# OBwod_sterowania_STM32.net
KiCad netlist of a schematic drawn in Altium Designer
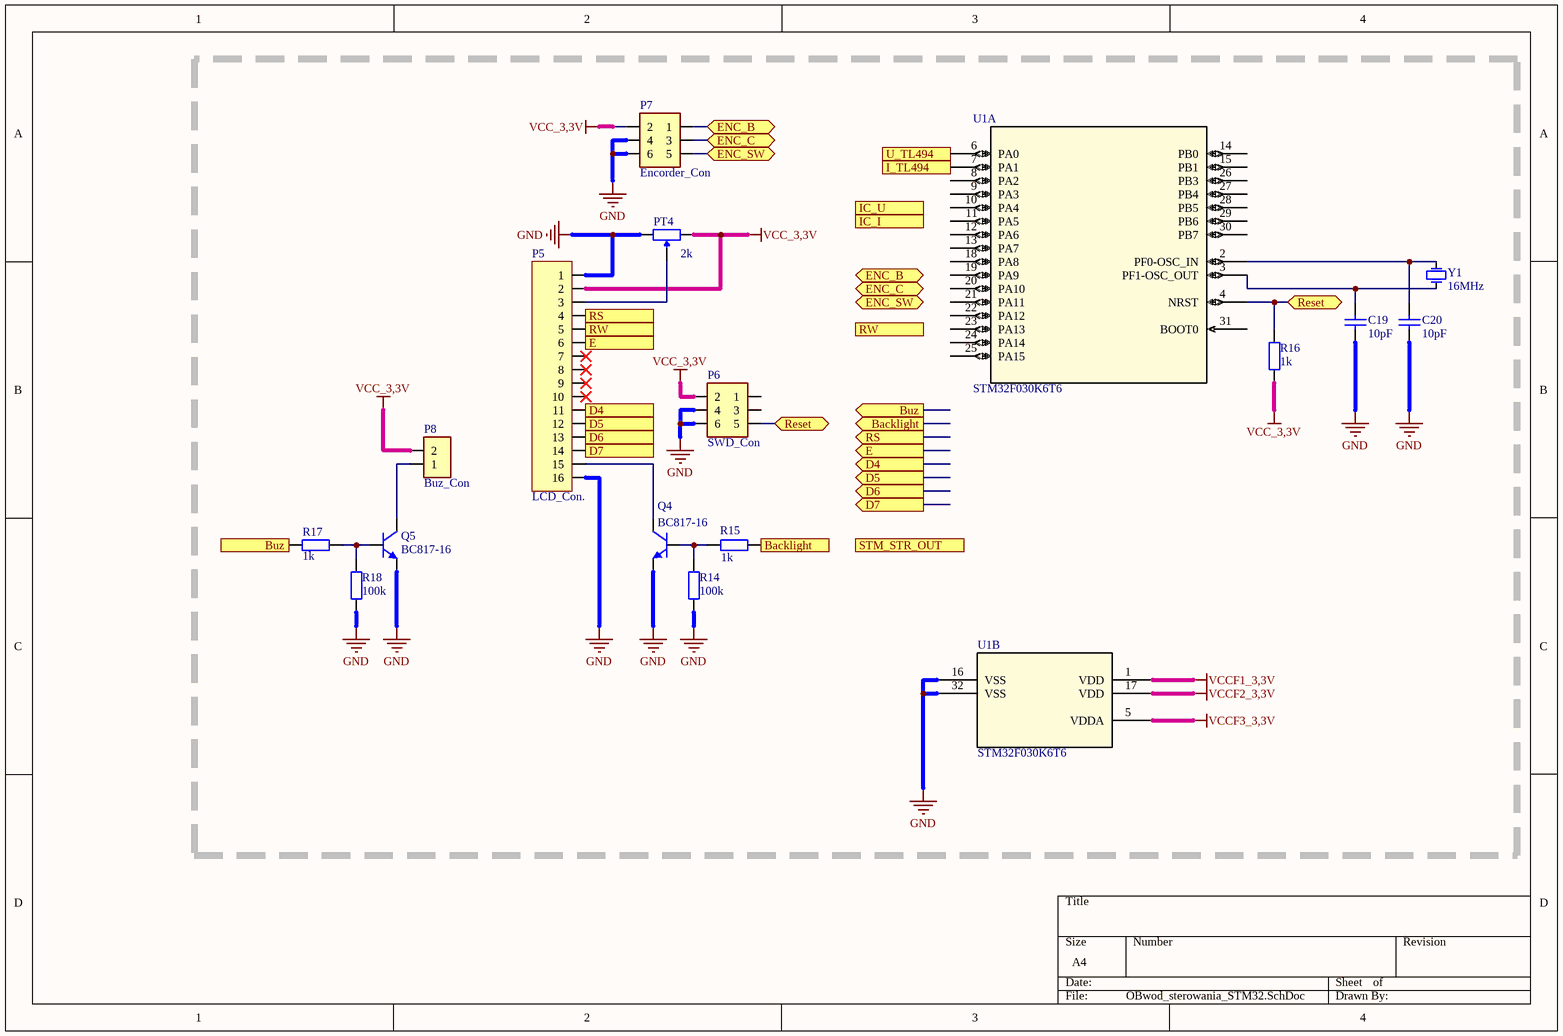
[diagram p0: OBwod_sterowania_STM32.SchDoc]

(export (version "E")
  (design (tool "Eeschema 10.0.6"))
  (components
    (comp (ref "C19")
      (value "Kondesator")
      (footprint "SMD-1206C")
      (fields (field (name "PARAMETR_1") "10pF"))
      (libsource (lib "MyLibrary") (part "Kondesator"))
    )
    (comp (ref "C20")
      (value "Kondesator")
      (footprint "SMD-1206C")
      (fields (field (name "PARAMETR_1") "10pF"))
      (libsource (lib "MyLibrary") (part "Kondesator"))
    )
    (comp (ref "P5")
      (value "LCD_Con.")
      (footprint "Header_Male 1x16")
      (description "Header, 16-Pin")
      (fields (field (name "PUBLISHER") "Altium Limited"))
      (libsource (lib "MyLibrary") (part "Header 16"))
    )
    (comp (ref "P6")
      (value "SWD_Con")
      (footprint "goldpin SMD 1,27")
      (libsource (lib "MyLibrary") (part "Header 2x3"))
    )
    (comp (ref "P7")
      (value "Encorder_Con")
      (footprint "Header_Male 2X3")
      (libsource (lib "MyLibrary") (part "Header 2x3"))
    )
    (comp (ref "P8")
      (value "Buz_Con")
      (footprint "Header_Male 1x2")
      (fields (field (name "PUBLISHER") "Altium Limited"))
      (libsource (lib "MyLibrary") (part "Header 2"))
    )
    (comp (ref "PT4")
      (value "Potentiometer")
      (footprint "Potecjomert")
      (description "Potentiometer montażowy wielobortowy")
      (fields (field (name "PARAMETR_1") "2k"))
      (libsource (lib "MyLibrary") (part "Potentiometer"))
    )
    (comp (ref "Q4")
      (value "BC817-16")
      (footprint "SOT323")
      (description "Tranzystor bipolarny PNP")
      (fields (field (name "OZNACZENIE") "BC817-16"))
      (libsource (lib "MyLibrary") (part "BC817-16"))
    )
    (comp (ref "Q5")
      (value "BC817-16")
      (footprint "SOT323")
      (description "Tranzystor bipolarny PNP")
      (fields (field (name "OZNACZENIE") "BC817-16"))
      (libsource (lib "MyLibrary") (part "BC817-16"))
    )
    (comp (ref "R14")
      (value "Rezystor")
      (footprint "SMD-1206-RES")
      (fields (field (name "PARAMETR_1") "100k"))
      (libsource (lib "") (part "Rezystor_1"))
    )
    (comp (ref "R15")
      (value "Rezystor")
      (footprint "SMD-1206-RES")
      (fields (field (name "PARAMETR_1") "1k"))
      (libsource (lib "MyLibrary") (part "Rezystor"))
    )
    (comp (ref "R16")
      (value "Rezystor")
      (footprint "SMD-1206-RES")
      (fields (field (name "PARAMETR_1") "1k"))
      (libsource (lib "") (part "Rezystor_2"))
    )
    (comp (ref "R17")
      (value "Rezystor")
      (footprint "SMD-1206-RES")
      (fields (field (name "PARAMETR_1") "1k"))
      (libsource (lib "") (part "Rezystor_2"))
    )
    (comp (ref "R18")
      (value "Rezystor")
      (footprint "SMD-1206-RES")
      (fields (field (name "PARAMETR_1") "100k"))
      (libsource (lib "MyLibrary") (part "Rezystor"))
    )
    (comp (ref "U1")
      (value "STM32F030K6T6")
      (footprint "LQFP-32")
      (description "No Description Available")
      (fields (field (name "COPYRIGHT") "Copyright (C) 2022 Ultra Librarian. All rights reserved."))
      (libsource (lib "MyLibrary") (part "STM32F030K6T6"))
    )
    (comp (ref "Y1") (value "16MHz") (footprint "HC49SM") (libsource (lib "MyLibrary") (part "Oscylator")))
  )
  (nets
    (net (code "1") (name "/Backlight") (class "Default")
      (node (ref "R15") (pin "1") (pinfunction "1_1") (pintype "passive"))
    )
    (net (code "2") (name "/Buz") (class "Default")
      (node (ref "R17") (pin "1") (pinfunction "1_1") (pintype "passive"))
    )
    (net (code "3") (name "/D4") (class "Default")
      (node (ref "P5") (pin "11") (pinfunction "11_11") (pintype "passive"))
    )
    (net (code "4") (name "/D5") (class "Default")
      (node (ref "P5") (pin "12") (pinfunction "12_12") (pintype "passive"))
    )
    (net (code "5") (name "/D6") (class "Default")
      (node (ref "P5") (pin "13") (pinfunction "13_13") (pintype "passive"))
    )
    (net (code "6") (name "/D7") (class "Default")
      (node (ref "P5") (pin "14") (pinfunction "14_14") (pintype "passive"))
    )
    (net (code "7") (name "/E") (class "Default")
      (node (ref "P5") (pin "6") (pinfunction "6_6") (pintype "passive"))
    )
    (net (code "8") (name "/ENC_B") (class "Default")
      (node (ref "P7") (pin "1") (pinfunction "1_1") (pintype "passive"))
    )
    (net (code "9") (name "/ENC_C") (class "Default")
      (node (ref "P7") (pin "3") (pinfunction "3_3") (pintype "passive"))
    )
    (net (code "10") (name "/ENC_SW") (class "Default")
      (node (ref "P7") (pin "5") (pinfunction "5_5") (pintype "passive"))
    )
    (net (code "13") (name "/I_TL494") (class "Default")
      (node (ref "U1") (pin "7") (pinfunction "PA1_7") (pintype "bidirectional"))
    )
    (net (code "14") (name "/RS") (class "Default")
      (node (ref "P5") (pin "4") (pinfunction "4_4") (pintype "passive"))
    )
    (net (code "15") (name "/RW") (class "Default")
      (node (ref "P5") (pin "5") (pinfunction "5_5") (pintype "passive"))
    )
    (net (code "16") (name "/Reset") (class "Default")
      (node (ref "P6") (pin "5") (pinfunction "5_5") (pintype "passive"))
      (node (ref "R16") (pin "2") (pinfunction "2_2") (pintype "passive"))
      (node (ref "U1") (pin "4") (pinfunction "NRST_4") (pintype "bidirectional"))
    )
    (net (code "18") (name "/U_TL494") (class "Default")
      (node (ref "U1") (pin "6") (pinfunction "PA0_6") (pintype "bidirectional"))
    )
    (net (code "19") (name "GND") (class "Default")
      (node (ref "C19") (pin "2") (pinfunction "2_2") (pintype "passive"))
      (node (ref "C20") (pin "1") (pinfunction "1_1") (pintype "passive"))
      (node (ref "P5") (pin "1") (pinfunction "1_1") (pintype "passive"))
      (node (ref "P5") (pin "16") (pinfunction "16_16") (pintype "passive"))
      (node (ref "P6") (pin "4") (pinfunction "4_4") (pintype "passive"))
      (node (ref "P6") (pin "6") (pinfunction "6_6") (pintype "passive"))
      (node (ref "P7") (pin "4") (pinfunction "4_4") (pintype "passive"))
      (node (ref "P7") (pin "6") (pinfunction "6_6") (pintype "passive"))
      (node (ref "PT4") (pin "1") (pinfunction "TOP_1") (pintype "passive"))
      (node (ref "Q4") (pin "2") (pinfunction "E_2") (pintype "passive"))
      (node (ref "Q5") (pin "2") (pinfunction "E_2") (pintype "passive"))
      (node (ref "R14") (pin "2") (pinfunction "2_2") (pintype "passive"))
      (node (ref "R18") (pin "2") (pinfunction "2_2") (pintype "passive"))
      (node (ref "U1") (pin "16") (pinfunction "VSS_16") (pintype "power_in"))
      (node (ref "U1") (pin "32") (pinfunction "VSS_32") (pintype "power_in"))
    )
    (net (code "20") (name "Net-(PT4-TAP)") (class "Default")
      (node (ref "P5") (pin "3") (pinfunction "3_3") (pintype "passive"))
      (node (ref "PT4") (pin "2") (pinfunction "TAP_2") (pintype "passive"))
    )
    (net (code "21") (name "Net-(Q4-B)") (class "Default")
      (node (ref "Q4") (pin "1") (pinfunction "B_1") (pintype "passive"))
      (node (ref "R14") (pin "1") (pinfunction "1_1") (pintype "passive"))
      (node (ref "R15") (pin "2") (pinfunction "2_2") (pintype "passive"))
    )
    (net (code "22") (name "Net-(Q4-C)") (class "Default")
      (node (ref "P5") (pin "15") (pinfunction "15_15") (pintype "passive"))
      (node (ref "Q4") (pin "3") (pinfunction "C_3") (pintype "passive"))
    )
    (net (code "23") (name "Net-(Q5-B)") (class "Default")
      (node (ref "Q5") (pin "1") (pinfunction "B_1") (pintype "passive"))
      (node (ref "R17") (pin "2") (pinfunction "2_2") (pintype "passive"))
      (node (ref "R18") (pin "1") (pinfunction "1_1") (pintype "passive"))
    )
    (net (code "24") (name "Net-(Q5-C)") (class "Default")
      (node (ref "P8") (pin "1") (pinfunction "1_1") (pintype "passive"))
      (node (ref "Q5") (pin "3") (pinfunction "C_3") (pintype "passive"))
    )
    (net (code "25") (name "Net-(U1A-PF0-OSC_IN)") (class "Default")
      (node (ref "C20") (pin "2") (pinfunction "2_2") (pintype "passive"))
      (node (ref "U1") (pin "2") (pinfunction "PF0-OSC_IN_2") (pintype "bidirectional"))
      (node (ref "Y1") (pin "2") (pinfunction "OSC2_2") (pintype "passive"))
    )
    (net (code "26") (name "Net-(U1A-PF1-OSC_OUT)") (class "Default")
      (node (ref "C19") (pin "1") (pinfunction "1_1") (pintype "passive"))
      (node (ref "U1") (pin "3") (pinfunction "PF1-OSC_OUT_3") (pintype "bidirectional"))
      (node (ref "Y1") (pin "1") (pinfunction "OSC1_1") (pintype "passive"))
    )
    (net (code "27") (name "VCCF1_3,3V") (class "Default")
      (node (ref "U1") (pin "1") (pinfunction "VDD_1") (pintype "power_in"))
    )
    (net (code "28") (name "VCCF2_3,3V") (class "Default")
      (node (ref "U1") (pin "17") (pinfunction "VDD_17") (pintype "power_in"))
    )
    (net (code "29") (name "VCCF3_3,3V") (class "Default")
      (node (ref "U1") (pin "5") (pinfunction "VDDA_5") (pintype "power_in"))
    )
    (net (code "30") (name "VCC_3,3V") (class "Default")
      (node (ref "P5") (pin "2") (pinfunction "2_2") (pintype "passive"))
      (node (ref "P6") (pin "2") (pinfunction "2_2") (pintype "passive"))
      (node (ref "P7") (pin "2") (pinfunction "2_2") (pintype "passive"))
      (node (ref "P8") (pin "2") (pinfunction "2_2") (pintype "passive"))
      (node (ref "PT4") (pin "3") (pinfunction "BOT_3") (pintype "passive"))
      (node (ref "R16") (pin "1") (pinfunction "1_1") (pintype "passive"))
    )
    (net (code "31") (name "unconnected-(P5-Pad7)") (class "Default")
      (node (ref "P5") (pin "7") (pinfunction "7_7") (pintype "passive+no_connect"))
    )
    (net (code "32") (name "unconnected-(P5-Pad8)") (class "Default")
      (node (ref "P5") (pin "8") (pinfunction "8_8") (pintype "passive+no_connect"))
    )
    (net (code "33") (name "unconnected-(P5-Pad9)") (class "Default")
      (node (ref "P5") (pin "9") (pinfunction "9_9") (pintype "passive+no_connect"))
    )
    (net (code "34") (name "unconnected-(P5-Pad10)") (class "Default")
      (node (ref "P5") (pin "10") (pinfunction "10_10") (pintype "passive+no_connect"))
    )
    (net (code "35") (name "unconnected-(P6-Pad1)") (class "Default")
      (node (ref "P6") (pin "1") (pinfunction "1_1") (pintype "passive"))
    )
    (net (code "36") (name "unconnected-(P6-Pad3)") (class "Default")
      (node (ref "P6") (pin "3") (pinfunction "3_3") (pintype "passive"))
    )
    (net (code "37") (name "unconnected-(U1A-BOOT0-Pad31)") (class "Default")
      (node (ref "U1") (pin "31") (pinfunction "BOOT0_31") (pintype "input"))
    )
    (net (code "38") (name "unconnected-(U1A-PA2-Pad8)") (class "Default")
      (node (ref "U1") (pin "8") (pinfunction "PA2_8") (pintype "bidirectional"))
    )
    (net (code "39") (name "unconnected-(U1A-PA3-Pad9)") (class "Default")
      (node (ref "U1") (pin "9") (pinfunction "PA3_9") (pintype "bidirectional"))
    )
    (net (code "40") (name "unconnected-(U1A-PA4-Pad10)") (class "Default")
      (node (ref "U1") (pin "10") (pinfunction "PA4_10") (pintype "bidirectional"))
    )
    (net (code "41") (name "unconnected-(U1A-PA5-Pad11)") (class "Default")
      (node (ref "U1") (pin "11") (pinfunction "PA5_11") (pintype "bidirectional"))
    )
    (net (code "42") (name "unconnected-(U1A-PA6-Pad12)") (class "Default")
      (node (ref "U1") (pin "12") (pinfunction "PA6_12") (pintype "bidirectional"))
    )
    (net (code "43") (name "unconnected-(U1A-PA7-Pad13)") (class "Default")
      (node (ref "U1") (pin "13") (pinfunction "PA7_13") (pintype "bidirectional"))
    )
    (net (code "44") (name "unconnected-(U1A-PA8-Pad18)") (class "Default")
      (node (ref "U1") (pin "18") (pinfunction "PA8_18") (pintype "bidirectional"))
    )
    (net (code "45") (name "unconnected-(U1A-PA9-Pad19)") (class "Default")
      (node (ref "U1") (pin "19") (pinfunction "PA9_19") (pintype "bidirectional"))
    )
    (net (code "46") (name "unconnected-(U1A-PA10-Pad20)") (class "Default")
      (node (ref "U1") (pin "20") (pinfunction "PA10_20") (pintype "bidirectional"))
    )
    (net (code "47") (name "unconnected-(U1A-PA11-Pad21)") (class "Default")
      (node (ref "U1") (pin "21") (pinfunction "PA11_21") (pintype "bidirectional"))
    )
    (net (code "48") (name "unconnected-(U1A-PA12-Pad22)") (class "Default")
      (node (ref "U1") (pin "22") (pinfunction "PA12_22") (pintype "bidirectional"))
    )
    (net (code "49") (name "unconnected-(U1A-PA13-Pad23)") (class "Default")
      (node (ref "U1") (pin "23") (pinfunction "PA13_23") (pintype "bidirectional"))
    )
    (net (code "50") (name "unconnected-(U1A-PA14-Pad24)") (class "Default")
      (node (ref "U1") (pin "24") (pinfunction "PA14_24") (pintype "bidirectional"))
    )
    (net (code "51") (name "unconnected-(U1A-PA15-Pad25)") (class "Default")
      (node (ref "U1") (pin "25") (pinfunction "PA15_25") (pintype "bidirectional"))
    )
    (net (code "52") (name "unconnected-(U1A-PB0-Pad14)") (class "Default")
      (node (ref "U1") (pin "14") (pinfunction "PB0_14") (pintype "bidirectional"))
    )
    (net (code "53") (name "unconnected-(U1A-PB1-Pad15)") (class "Default")
      (node (ref "U1") (pin "15") (pinfunction "PB1_15") (pintype "bidirectional"))
    )
    (net (code "54") (name "unconnected-(U1A-PB3-Pad26)") (class "Default")
      (node (ref "U1") (pin "26") (pinfunction "PB3_26") (pintype "bidirectional"))
    )
    (net (code "55") (name "unconnected-(U1A-PB4-Pad27)") (class "Default")
      (node (ref "U1") (pin "27") (pinfunction "PB4_27") (pintype "bidirectional"))
    )
    (net (code "56") (name "unconnected-(U1A-PB5-Pad28)") (class "Default")
      (node (ref "U1") (pin "28") (pinfunction "PB5_28") (pintype "bidirectional"))
    )
    (net (code "57") (name "unconnected-(U1A-PB6-Pad29)") (class "Default")
      (node (ref "U1") (pin "29") (pinfunction "PB6_29") (pintype "bidirectional"))
    )
    (net (code "58") (name "unconnected-(U1A-PB7-Pad30)") (class "Default")
      (node (ref "U1") (pin "30") (pinfunction "PB7_30") (pintype "bidirectional"))
    )
  )
)
